# LiIonLader_1ZelleMax500mA.net
KiCad netlist of a schematic drawn in EAGLE
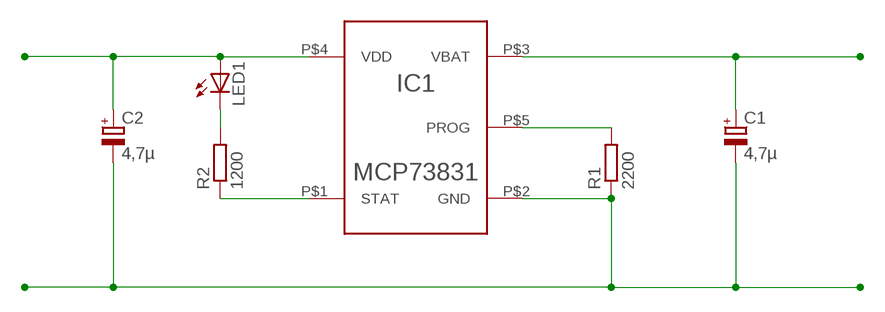
[diagram p0: schematic, sheet 1]

(export (version "E")
  (design (tool "Eeschema 10.0.6"))
  (components
    (comp (ref "C1")
      (value "4,7µ")
      (footprint "eagle-import:E1,8-4")
      (libsource (lib "eagle-import") (part "CPOL-EUE1.8-4"))
    )
    (comp (ref "C2")
      (value "4,7µ")
      (footprint "eagle-import:E1,8-4")
      (libsource (lib "eagle-import") (part "CPOL-EUE1.8-4"))
    )
    (comp (ref "IC1")
      (value "MCP73831")
      (footprint "eagle-import:SOT-23-5")
      (libsource (lib "eagle-import") (part "MCP73831"))
    )
    (comp (ref "LED1")
      (value "LED3MM")
      (footprint "eagle-import:LED3MM")
      (libsource (lib "eagle-import") (part "LED3MM"))
    )
    (comp (ref "R1")
      (value "2200")
      (footprint "eagle-import:0204_5")
      (libsource (lib "eagle-import") (part "R-EU_0204/5"))
    )
    (comp (ref "R2")
      (value "1200")
      (footprint "eagle-import:0204_5")
      (libsource (lib "eagle-import") (part "R-EU_0204/5"))
    )
  )
  (nets
    (net (code "1") (name "Net-(IC1-GND)") (class "Default")
      (node (ref "C1") (pin "-") (pinfunction "-_-") (pintype "passive"))
      (node (ref "C2") (pin "-") (pinfunction "-_-") (pintype "passive"))
      (node (ref "IC1") (pin "P$2") (pinfunction "GND_P$2") (pintype "power_in"))
      (node (ref "R1") (pin "1") (pinfunction "1_1") (pintype "passive"))
    )
    (net (code "2") (name "Net-(IC1-PROG)") (class "Default")
      (node (ref "IC1") (pin "P$5") (pinfunction "PROG_P$5") (pintype "passive"))
      (node (ref "R1") (pin "2") (pinfunction "2_2") (pintype "passive"))
    )
    (net (code "3") (name "Net-(IC1-STAT)") (class "Default")
      (node (ref "IC1") (pin "P$1") (pinfunction "STAT_P$1") (pintype "open_collector"))
      (node (ref "R2") (pin "1") (pinfunction "1_1") (pintype "passive"))
    )
    (net (code "4") (name "Net-(IC1-VBAT)") (class "Default")
      (node (ref "C1") (pin "+") (pinfunction "+_+") (pintype "passive"))
      (node (ref "IC1") (pin "P$3") (pinfunction "VBAT_P$3") (pintype "output"))
    )
    (net (code "5") (name "Net-(IC1-VDD)") (class "Default")
      (node (ref "C2") (pin "+") (pinfunction "+_+") (pintype "passive"))
      (node (ref "IC1") (pin "P$4") (pinfunction "VDD_P$4") (pintype "power_in"))
      (node (ref "LED1") (pin "A") (pinfunction "A_A") (pintype "passive"))
    )
    (net (code "6") (name "Net-(LED1-C)") (class "Default")
      (node (ref "LED1") (pin "K") (pinfunction "C_K") (pintype "passive"))
      (node (ref "R2") (pin "2") (pinfunction "2_2") (pintype "passive"))
    )
  )
)
